# PowerManagement.net
KiCad netlist of a schematic drawn in Altium Designer
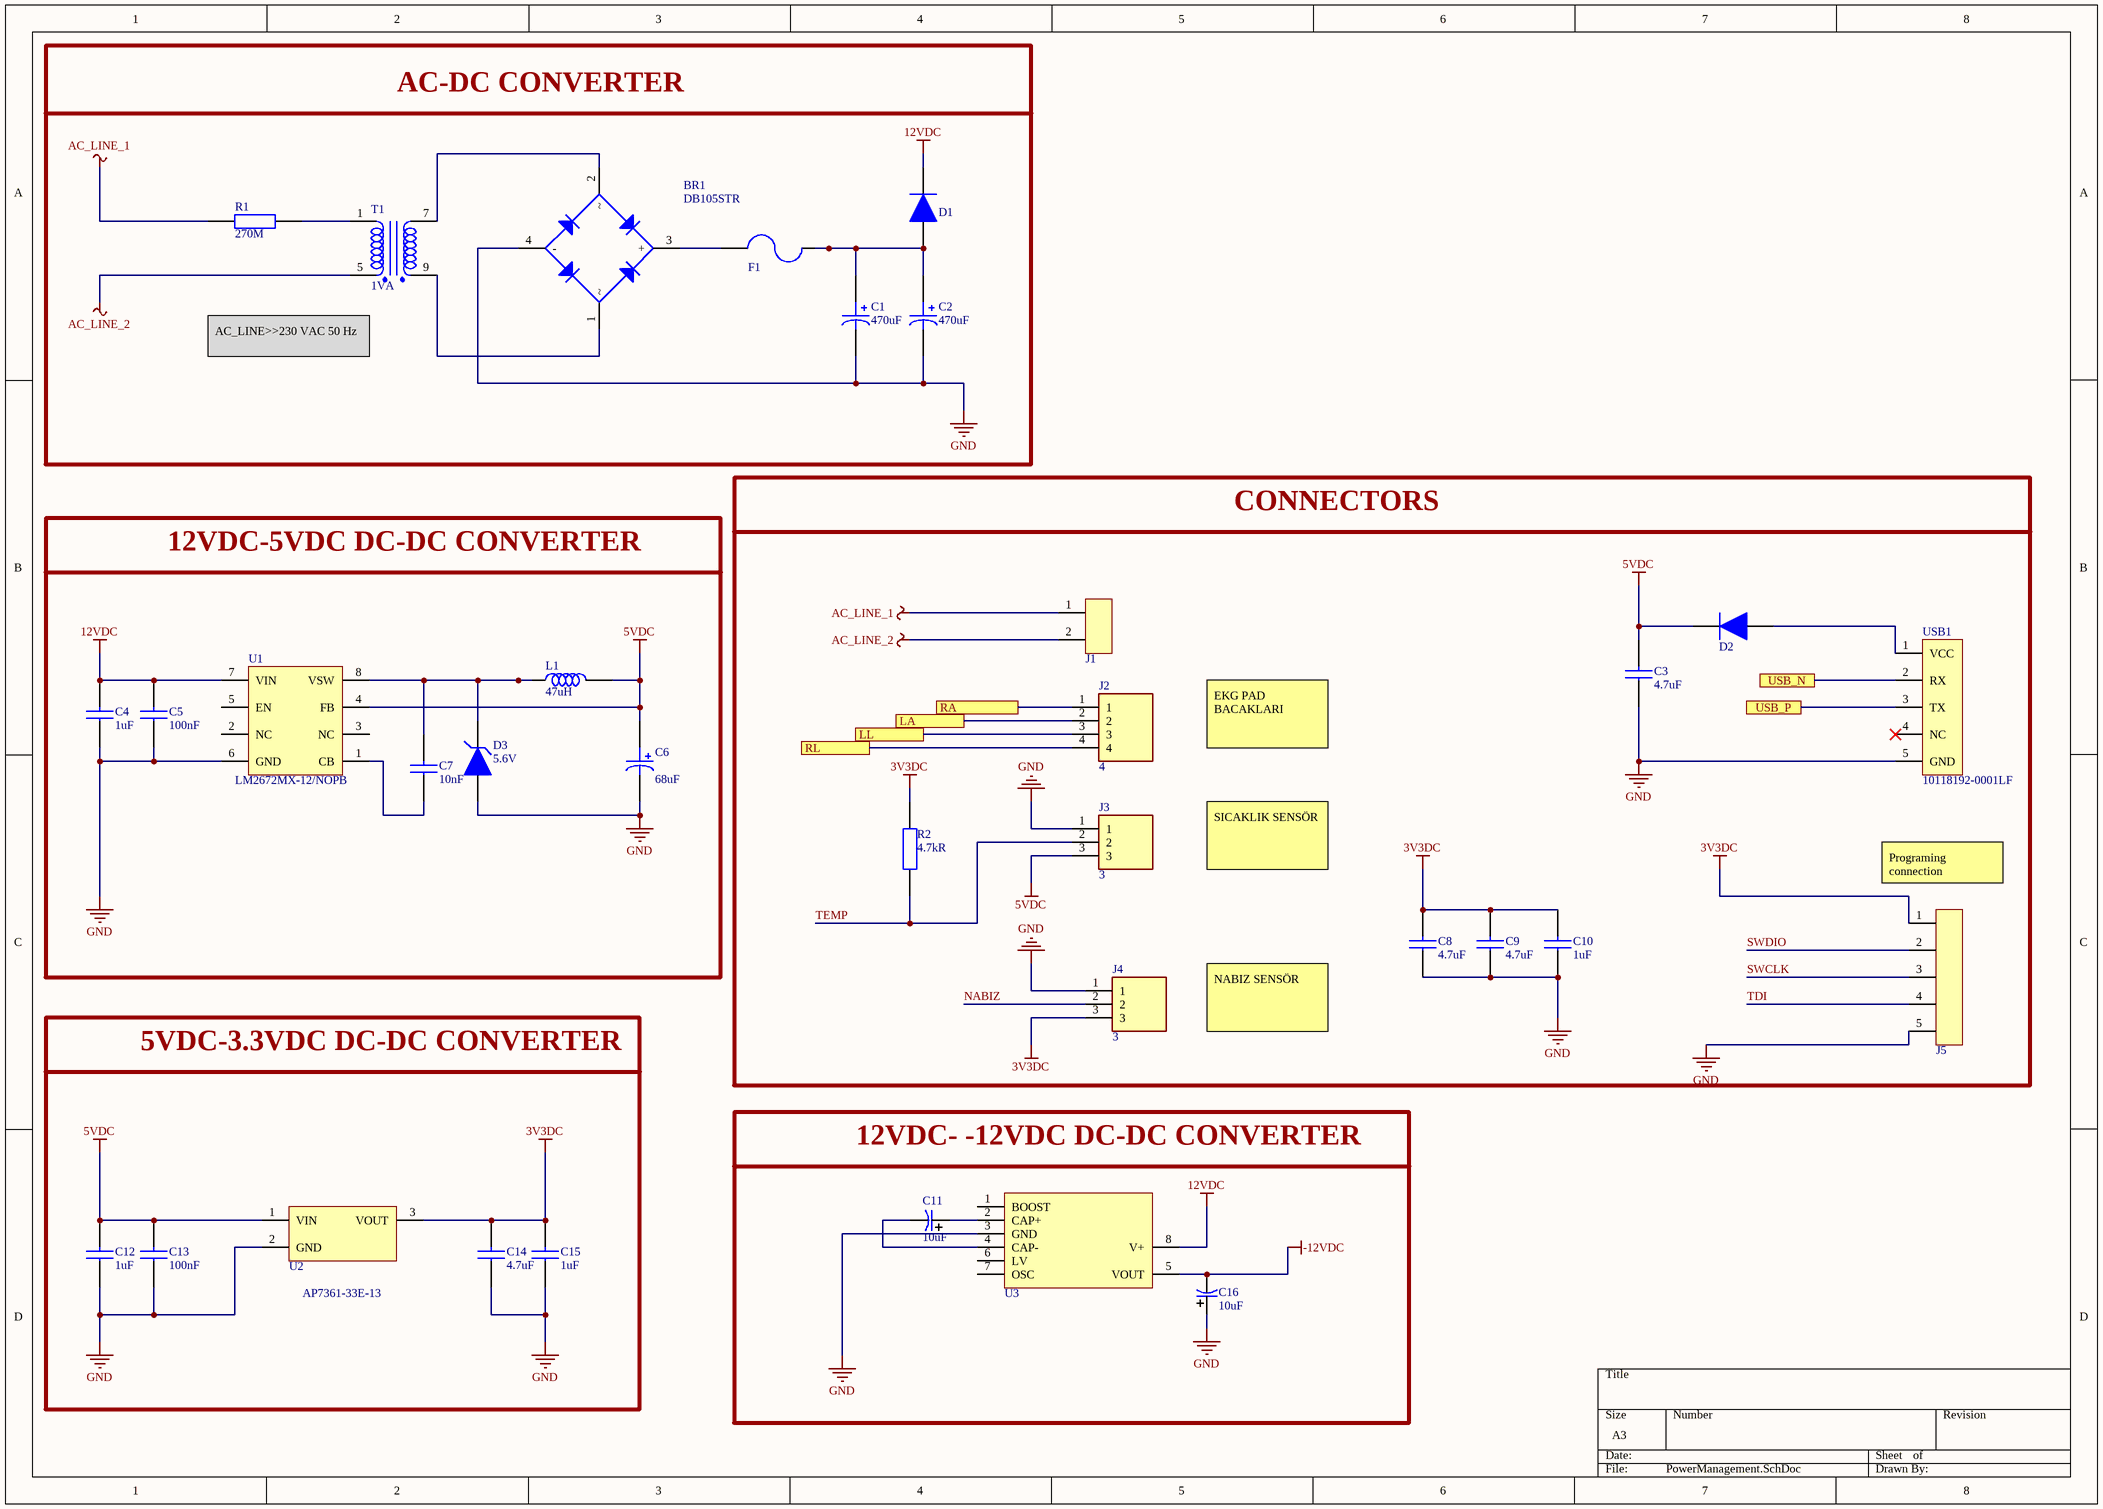
[diagram p0: PowerManagement.SchDoc]

(export (version "E")
  (design (tool "Eeschema 10.0.6"))
  (components
    (comp (ref "BR1")
      (value "DB105STR")
      (footprint "DB105STR")
      (fields (field (name "MANUFACTURER") "SMC") (field (name "DESIGNED BY") "TALAT"))
      (libsource (lib "Udemy_Library") (part "DB105STR"))
    )
    (comp (ref "C1")
      (value "ESH477M050AH4AA")
      (footprint "CAP_RADİAL_D10_P5")
      (description "Cap, 470UF, 50V, Alu Elec, Radial")
      (fields
        (field (name "MANUFACTURER") "KEMET")
        (field (name "TOLERANCE") "20%")
        (field (name "CAPACITANCE") "470uF")
        (field (name "DESIGNED BY") "TALAT")
      )
      (libsource (lib "Udemy_Library") (part "ESH477M050AH4AA"))
    )
    (comp (ref "C2")
      (value "ESH477M050AH4AA")
      (footprint "CAP_RADİAL_D10_P5")
      (description "Cap, 470UF, 50V, Alu Elec, Radial")
      (fields
        (field (name "MANUFACTURER") "KEMET")
        (field (name "TOLERANCE") "20%")
        (field (name "CAPACITANCE") "470uF")
        (field (name "DESIGNED BY") "TALAT")
      )
      (libsource (lib "Udemy_Library") (part "ESH477M050AH4AA"))
    )
    (comp (ref "C3")
      (value "CL21A475KAQNNNE")
      (footprint "CAP_0805")
      (description "CAP CER 4.7uF %10 0805")
      (fields
        (field (name "MANUFACTURER") "Samsung")
        (field (name "TOLERANCE") "10%")
        (field (name "CAPACITANCE") "4.7uF")
        (field (name "DESIGNED BY") "TALAT")
      )
      (libsource (lib "Udemy_Library") (part "CAP CER 4.7uF 0805"))
    )
    (comp (ref "C4")
      (value "CL21B105KBFNNNE")
      (footprint "CAP_0805")
      (description "CAP CER 1uF %10 0805")
      (fields
        (field (name "MANUFACTURER") "Samsung")
        (field (name "TOLERANCE") "10%")
        (field (name "CAPACITANCE") "1uF")
        (field (name "DESIGNED BY") "TALAT")
      )
      (libsource (lib "Udemy_Library") (part "CAP CER 1uF 0805"))
    )
    (comp (ref "C5")
      (value "CL21B104KBCNNNC")
      (footprint "CAP_0805")
      (description "CAP CER 100nF %10 0805")
      (fields
        (field (name "MANUFACTURER") "Samsung")
        (field (name "TOLERANCE") "10%")
        (field (name "CAPACITANCE") "100nF")
        (field (name "DESIGNED BY") "TALAT")
      )
      (libsource (lib "Udemy_Library") (part "CAP CER 100nF 0805"))
    )
    (comp (ref "C6")
      (value "EEV686M035A9HAA")
      (footprint "CAP_EEVseries")
      (description "Cap Aluminum Lytic 68uF 35V 20% (6.3 X 7.7mm) SMD 280mA 2000h 105C T/R")
      (fields
        (field (name "MANUFACTURER") "KEMET")
        (field (name "TOLERANCE") "20%")
        (field (name "CAPACITANCE") "68uF")
      )
      (libsource (lib "Udemy_Library") (part "CAP ALU 68uF"))
    )
    (comp (ref "C7")
      (value "0603B103K160CT")
      (footprint "CAP_0603")
      (description "CAP CER 10nF %10 0603")
      (fields
        (field (name "MANUFACTURER") "Walsin Technologies")
        (field (name "TOLERANCE") "10%")
        (field (name "CAPACITANCE") "10nF")
        (field (name "DESIGNED BY") "TALAT")
      )
      (libsource (lib "Udemy_Library") (part "CAP CER 10nF 0603"))
    )
    (comp (ref "C8")
      (value "CL21A475KAQNNNE")
      (footprint "CAP_0805")
      (description "CAP CER 4.7uF %10 0805")
      (fields
        (field (name "MANUFACTURER") "Samsung")
        (field (name "TOLERANCE") "10%")
        (field (name "CAPACITANCE") "4.7uF")
        (field (name "DESIGNED BY") "TALAT")
      )
      (libsource (lib "Udemy_Library") (part "CAP CER 4.7uF 0805"))
    )
    (comp (ref "C9")
      (value "CL21A475KAQNNNE")
      (footprint "CAP_0805")
      (description "CAP CER 4.7uF %10 0805")
      (fields
        (field (name "MANUFACTURER") "Samsung")
        (field (name "TOLERANCE") "10%")
        (field (name "CAPACITANCE") "4.7uF")
        (field (name "DESIGNED BY") "TALAT")
      )
      (libsource (lib "Udemy_Library") (part "CAP CER 4.7uF 0805"))
    )
    (comp (ref "C10")
      (value "CL21B105KBFNNNE")
      (footprint "CAP_0805")
      (description "CAP CER 1uF %10 0805")
      (fields
        (field (name "MANUFACTURER") "Samsung")
        (field (name "TOLERANCE") "10%")
        (field (name "CAPACITANCE") "1uF")
        (field (name "DESIGNED BY") "TALAT")
      )
      (libsource (lib "Udemy_Library") (part "CAP CER 1uF 0805"))
    )
    (comp (ref "C11")
      (value "CAP ALU 10uF")
      (footprint "A700V_KEM")
      (description "CAP ALUM POLY 10UF 20% 12.5V SMD")
      (fields
        (field (name "MANUFACTURER") "KEMET")
        (field (name "MANUFACTURER PART NUMBER") "A700V106M12RATE040")
        (field (name "CAPACITANCE") "10uF")
      )
      (libsource (lib "Udemy_Library") (part "CAP ALU 10uF"))
    )
    (comp (ref "C12")
      (value "CL21B105KBFNNNE")
      (footprint "CAP_0805")
      (description "CAP CER 1uF %10 0805")
      (fields
        (field (name "MANUFACTURER") "Samsung")
        (field (name "TOLERANCE") "10%")
        (field (name "CAPACITANCE") "1uF")
        (field (name "DESIGNED BY") "TALAT")
      )
      (libsource (lib "Udemy_Library") (part "CAP CER 1uF 0805"))
    )
    (comp (ref "C13")
      (value "C0603C104K5RACTU")
      (footprint "CAP_0603")
      (description "CAP CER 100nF %10 0603 SMD")
      (fields
        (field (name "MANUFACTURER") "KEMET")
        (field (name "CAPACITANCE") "100nF")
        (field (name "TOLERANCE") "10%")
        (field (name "DESIGNED BY") "TALAT")
      )
      (libsource (lib "Udemy_Library") (part "CAP CER 100nF 0603"))
    )
    (comp (ref "C14")
      (value "CL21A475KAQNNNE")
      (footprint "CAP_0805")
      (description "CAP CER 4.7uF %10 0805")
      (fields
        (field (name "MANUFACTURER") "Samsung")
        (field (name "TOLERANCE") "10%")
        (field (name "CAPACITANCE") "4.7uF")
        (field (name "DESIGNED BY") "TALAT")
      )
      (libsource (lib "Udemy_Library") (part "CAP CER 4.7uF 0805"))
    )
    (comp (ref "C15")
      (value "CL21B105KBFNNNE")
      (footprint "CAP_0805")
      (description "CAP CER 1uF %10 0805")
      (fields
        (field (name "MANUFACTURER") "Samsung")
        (field (name "TOLERANCE") "10%")
        (field (name "CAPACITANCE") "1uF")
        (field (name "DESIGNED BY") "TALAT")
      )
      (libsource (lib "Udemy_Library") (part "CAP CER 1uF 0805"))
    )
    (comp (ref "C16")
      (value "CAP ALU 10uF")
      (footprint "A700V_KEM")
      (description "CAP ALUM POLY 10UF 20% 12.5V SMD")
      (fields
        (field (name "MANUFACTURER") "KEMET")
        (field (name "MANUFACTURER PART NUMBER") "A700V106M12RATE040")
        (field (name "CAPACITANCE") "10uF")
      )
      (libsource (lib "Udemy_Library") (part "CAP ALU 10uF"))
    )
    (comp (ref "D1")
      (value "1N4148WS")
      (footprint "SOD323F")
      (description "Diode, Single, 75 V, 150 mA, 1 V, 4 ns")
      (fields
        (field (name "MANUFACTURER") "ON Semiconductor / Fairchild")
        (field (name "DESIGNED BY") "TALAT")
      )
      (libsource (lib "Udemy_Library") (part "1N4148WS"))
    )
    (comp (ref "D2")
      (value "1N4148WS")
      (footprint "SOD323F")
      (description "Diode, Single, 75 V, 150 mA, 1 V, 4 ns")
      (fields
        (field (name "MANUFACTURER") "ON Semiconductor / Fairchild")
        (field (name "DESIGNED BY") "TALAT")
      )
      (libsource (lib "Udemy_Library") (part "1N4148WS"))
    )
    (comp (ref "D3")
      (value "1SMB5919BT3G")
      (footprint "SMB")
      (description "Diode Zener Single 5.6V 5% 3W 2-Pin SMB T/R")
      (fields
        (field (name "MANUFACTURER") "ON Semiconductor")
        (field (name "TOLERANCE") "5%")
        (field (name "WORKING VOLTAGE") "5.6V")
        (field (name "DESIGNED BY") "TALAT")
      )
      (libsource (lib "Udemy_Library") (part "1SMB5919BT3G"))
    )
    (comp (ref "F1")
      (value "3413.0216.22")
      (footprint "3413.0216.2")
      (description "FUSE BRD MNT 1A 32VAC 63VDC 1206")
      (fields (field (name "MANUFACTURER") "Schurter") (field (name "DESIGNED BY") "TALAT"))
      (libsource (lib "Udemy_Library") (part "FUSE 3413.0216.22"))
    )
    (comp (ref "J1")
      (value "TBP01R1-508-02BE")
      (footprint "TBP01R1-508")
      (description "Conn Shrouded Header HDR 2 POS 5.08mm Solder RA Side Entry Thru-Hole Bag")
      (fields (field (name "MANUFACTURER") "CUI") (field (name "DESIGNED BY") "TALAT"))
      (libsource (lib "Udemy_Library") (part "TBP01R1-508-02BE"))
    )
    (comp (ref "J2") (value "4") (footprint "796644-4") (libsource (lib "Udemy_Library") (part "796644-4")))
    (comp (ref "J3")
      (value "3")
      (footprint "TBP01R1-508-03BE")
      (fields
        (field (name "MANUFACTURER") "CUI")
        (field (name "MANUFACTURER PART NUMBER") "TBP01R1-508-03BE")
      )
      (libsource (lib "Udemy_Library") (part "TBP01R1-508-03BE"))
    )
    (comp (ref "J4")
      (value "3")
      (footprint "TBP01R1-508-03BE")
      (fields
        (field (name "MANUFACTURER") "CUI")
        (field (name "MANUFACTURER PART NUMBER") "TBP01R1-508-03BE")
      )
      (libsource (lib "Udemy_Library") (part "TBP01R1-508-03BE"))
    )
    (comp (ref "J5")
      (value "SMH-105-02-L-S")
      (footprint "PINHEADER1X5_RA")
      (description ".100 C.L. HORIZONTAL SMT SOCKET")
      (fields (field (name "MANUFACTURER") "Samtec") (field (name "DESIGNED BY") "TALAT"))
      (libsource (lib "Udemy_Library") (part "SMH-105-02-L-S"))
    )
    (comp (ref "L1")
      (value "78438335470")
      (footprint "IND_1212")
      (description "FIXED IND 47UH 390MA 2.3 OHM SMD")
      (fields
        (field (name "MANUFACTURER") "Wurth Electronics")
        (field (name "TOLERANCE") "30%")
        (field (name "INDUCTANCE") "47uH")
        (field (name "DESIGNED BY") "TALAT")
      )
      (libsource (lib "Udemy_Library") (part "IND 47uH"))
    )
    (comp (ref "R1")
      (value "5WD27")
      (footprint "RES_AXIAL_W")
      (description "Resistor 5 Watt Cermet Wirewound Flameproof .27 Ohm 5% Axial Lead")
      (fields
        (field (name "MANUFACTURER") "NTE Electronics")
        (field (name "TOLERANCE") "5%")
        (field (name "RESISTANCE") "270M")
        (field (name "DESIGNED BY") "TALAT")
      )
      (libsource (lib "Udemy_Library") (part "5WD27"))
    )
    (comp (ref "R2")
      (value "RC0603JR-074K7L")
      (footprint "RES_0603")
      (description "RES 4K7 %5 OHM 0603 SMD")
      (fields
        (field (name "MANUFACTURER") "Yageo")
        (field (name "TOLERANCE") "5%")
        (field (name "RESISTANCE") "4.7kR")
        (field (name "DESIGNED BY") "TALAT")
      )
      (libsource (lib "Udemy_Library") (part "RES 4K7 OHM 0603"))
    )
    (comp (ref "T1")
      (value "BV302S12010-ZU")
      (footprint "BV302S")
      (description "PWR XFMR LAMINATED 1VA TH")
      (fields
        (field (name "MANUFACTURER") "Zettler Magnetics")
        (field (name "RATED POWER") "1VA")
        (field (name "DESIGNED BY") "TALAT")
      )
      (libsource (lib "Udemy_Library") (part "BV302S12010-ZU"))
    )
    (comp (ref "U1")
      (value "LM2672MX-12/NOPB")
      (footprint "SOIC8")
      (description "IC REG BUCK 12V 1A 8-SOIC")
      (fields (field (name "MANUFACTURER") "TI National Semiconductor") (field (name "DESIGNED BY") "TALAT"))
      (libsource (lib "Udemy_Library") (part "LM2672MX-12/NOPB"))
    )
    (comp (ref "U2")
      (value "AP7361-33E-13")
      (footprint "SOT223")
      (description "LDO Regulator Pos 3.3V 1A 4-Pin(3+Tab) SOT-223 T/R")
      (fields (field (name "MANUFACTURER") "Diodes") (field (name "DESIGNED BY") "TALAT"))
      (libsource (lib "Udemy_Library") (part "AP7361-33E-13"))
    )
    (comp (ref "U3")
      (value "LTC1044AIS8#TRPBF")
      (footprint "SOIC8")
      (description "IC REG SWTCHD CAP INV 20MA 8SOIC")
      (fields
        (field (name "MANUFACTURER") "Analog Devices / Linear Technology")
        (field (name "DESIGNED BY") "Talat")
      )
      (libsource (lib "Udemy_Library") (part "LTC1044A"))
    )
    (comp (ref "USB1")
      (value "10118192-0001LF")
      (footprint "MICRO_B_USB")
      (description "CONN RCPT USB2.0 MICRO B SMD R/A")
      (fields (field (name "MANUFACTURER") "Amphenol FCI") (field (name "DESIGNED BY") "TALAT"))
      (libsource (lib "Udemy_Library") (part "Micro B USB Connector"))
    )
  )
  (nets
    (net (code "1") (name "-12VDC") (class "Default")
      (node (ref "C16") (pin "2") (pinfunction "2_2") (pintype "passive"))
      (node (ref "U3") (pin "5") (pinfunction "VOUT_5") (pintype "passive"))
    )
    (net (code "2") (name "/LA") (class "Default")
      (node (ref "J2") (pin "2") (pinfunction "2_2") (pintype "passive"))
    )
    (net (code "3") (name "/LL") (class "Default")
      (node (ref "J2") (pin "3") (pinfunction "3_3") (pintype "passive"))
    )
    (net (code "4") (name "/NABIZ") (class "Default")
      (node (ref "J4") (pin "2") (pinfunction "2_2") (pintype "passive"))
    )
    (net (code "5") (name "/RA") (class "Default")
      (node (ref "J2") (pin "1") (pinfunction "1_1") (pintype "passive"))
    )
    (net (code "6") (name "/RL") (class "Default")
      (node (ref "J2") (pin "4") (pinfunction "4_4") (pintype "passive"))
    )
    (net (code "7") (name "/SWCLK") (class "Default")
      (node (ref "J5") (pin "3") (pinfunction "3_3") (pintype "power_in"))
    )
    (net (code "8") (name "/SWDIO") (class "Default")
      (node (ref "J5") (pin "2") (pinfunction "2_2") (pintype "power_in"))
    )
    (net (code "9") (name "/TDI") (class "Default")
      (node (ref "J5") (pin "4") (pinfunction "4_4") (pintype "power_in"))
    )
    (net (code "10") (name "/TEMP") (class "Default")
      (node (ref "J3") (pin "2") (pinfunction "2_2") (pintype "passive"))
      (node (ref "R2") (pin "1") (pinfunction "1_1") (pintype "passive"))
    )
    (net (code "11") (name "/USB_N") (class "Default")
      (node (ref "USB1") (pin "2") (pinfunction "RX_2") (pintype "power_in"))
    )
    (net (code "12") (name "/USB_P") (class "Default")
      (node (ref "USB1") (pin "3") (pinfunction "TX_3") (pintype "power_in"))
    )
    (net (code "13") (name "3V3DC") (class "Default")
      (node (ref "C10") (pin "2") (pinfunction "2_2") (pintype "passive"))
      (node (ref "C14") (pin "2") (pinfunction "2_2") (pintype "passive"))
      (node (ref "C15") (pin "2") (pinfunction "2_2") (pintype "passive"))
      (node (ref "C8") (pin "2") (pinfunction "2_2") (pintype "passive"))
      (node (ref "C9") (pin "2") (pinfunction "2_2") (pintype "passive"))
      (node (ref "J4") (pin "3") (pinfunction "3_3") (pintype "passive"))
      (node (ref "J5") (pin "1") (pinfunction "1_1") (pintype "power_in"))
      (node (ref "R2") (pin "2") (pinfunction "2_2") (pintype "passive"))
      (node (ref "U2") (pin "3") (pinfunction "VOUT_3") (pintype "passive"))
    )
    (net (code "14") (name "5VDC") (class "Default")
      (node (ref "C12") (pin "2") (pinfunction "2_2") (pintype "passive"))
      (node (ref "C13") (pin "2") (pinfunction "2_2") (pintype "passive"))
      (node (ref "C3") (pin "2") (pinfunction "2_2") (pintype "passive"))
      (node (ref "C6") (pin "1") (pinfunction "1_1") (pintype "passive"))
      (node (ref "D2") (pin "1") (pinfunction "1_1") (pintype "power_in"))
      (node (ref "J3") (pin "3") (pinfunction "3_3") (pintype "passive"))
      (node (ref "L1") (pin "2") (pinfunction "2_2") (pintype "passive"))
      (node (ref "U1") (pin "4") (pinfunction "FB_4") (pintype "passive"))
      (node (ref "U2") (pin "1") (pinfunction "VIN_1") (pintype "passive"))
    )
    (net (code "15") (name "12VDC") (class "Default")
      (node (ref "C4") (pin "2") (pinfunction "2_2") (pintype "passive"))
      (node (ref "C5") (pin "2") (pinfunction "2_2") (pintype "passive"))
      (node (ref "D1") (pin "1") (pinfunction "1_1") (pintype "power_in"))
      (node (ref "U1") (pin "7") (pinfunction "VIN_7") (pintype "passive"))
      (node (ref "U3") (pin "8") (pinfunction "V+_8") (pintype "passive"))
    )
    (net (code "16") (name "AC_LINE_1") (class "Default")
      (node (ref "J1") (pin "1") (pinfunction "1_1") (pintype "power_in"))
      (node (ref "R1") (pin "1") (pinfunction "1_1") (pintype "passive"))
    )
    (net (code "17") (name "AC_LINE_2") (class "Default")
      (node (ref "J1") (pin "2") (pinfunction "2_2") (pintype "power_in"))
      (node (ref "T1") (pin "5") (pinfunction "5_5") (pintype "passive"))
    )
    (net (code "18") (name "GND") (class "Default")
      (node (ref "BR1") (pin "4") (pinfunction "-_4") (pintype "passive"))
      (node (ref "C1") (pin "2") (pinfunction "2_2") (pintype "passive"))
      (node (ref "C10") (pin "1") (pinfunction "1_1") (pintype "passive"))
      (node (ref "C12") (pin "1") (pinfunction "1_1") (pintype "passive"))
      (node (ref "C13") (pin "1") (pinfunction "1_1") (pintype "passive"))
      (node (ref "C14") (pin "1") (pinfunction "1_1") (pintype "passive"))
      (node (ref "C15") (pin "1") (pinfunction "1_1") (pintype "passive"))
      (node (ref "C16") (pin "1") (pinfunction "1_1") (pintype "passive"))
      (node (ref "C2") (pin "2") (pinfunction "2_2") (pintype "passive"))
      (node (ref "C3") (pin "1") (pinfunction "1_1") (pintype "passive"))
      (node (ref "C4") (pin "1") (pinfunction "1_1") (pintype "passive"))
      (node (ref "C5") (pin "1") (pinfunction "1_1") (pintype "passive"))
      (node (ref "C6") (pin "2") (pinfunction "2_2") (pintype "passive"))
      (node (ref "C8") (pin "1") (pinfunction "1_1") (pintype "passive"))
      (node (ref "C9") (pin "1") (pinfunction "1_1") (pintype "passive"))
      (node (ref "D3") (pin "A") (pinfunction "A_A") (pintype "passive"))
      (node (ref "J3") (pin "1") (pinfunction "1_1") (pintype "passive"))
      (node (ref "J4") (pin "1") (pinfunction "1_1") (pintype "passive"))
      (node (ref "J5") (pin "5") (pinfunction "5_5") (pintype "power_in"))
      (node (ref "U1") (pin "6") (pinfunction "GND_6") (pintype "passive"))
      (node (ref "U2") (pin "2") (pinfunction "GND_2") (pintype "passive"))
      (node (ref "U3") (pin "3") (pinfunction "GND_3") (pintype "passive"))
      (node (ref "USB1") (pin "5") (pinfunction "GND_5") (pintype "power_in"))
    )
    (net (code "19") (name "Net-(BR1-+)") (class "Default")
      (node (ref "BR1") (pin "3") (pinfunction "+_3") (pintype "passive"))
      (node (ref "F1") (pin "1") (pinfunction "1_1") (pintype "passive"))
    )
    (net (code "20") (name "Net-(BR1-~-Pad1)") (class "Default")
      (node (ref "BR1") (pin "1") (pinfunction "~_1") (pintype "passive"))
      (node (ref "T1") (pin "9") (pinfunction "9_9") (pintype "passive"))
    )
    (net (code "21") (name "Net-(BR1-~-Pad2)") (class "Default")
      (node (ref "BR1") (pin "2") (pinfunction "~_2") (pintype "passive"))
      (node (ref "T1") (pin "7") (pinfunction "7_7") (pintype "passive"))
    )
    (net (code "22") (name "Net-(C1-Pad1)") (class "Default")
      (node (ref "C1") (pin "1") (pinfunction "1_1") (pintype "passive"))
      (node (ref "C2") (pin "1") (pinfunction "1_1") (pintype "passive"))
      (node (ref "D1") (pin "2") (pinfunction "2_2") (pintype "power_in"))
      (node (ref "F1") (pin "2") (pinfunction "2_2") (pintype "passive"))
    )
    (net (code "23") (name "Net-(R1-Pad2)") (class "Default")
      (node (ref "R1") (pin "2") (pinfunction "2_2") (pintype "passive"))
      (node (ref "T1") (pin "1") (pinfunction "1_1") (pintype "passive"))
    )
    (net (code "24") (name "Net-(U1-CB)") (class "Default")
      (node (ref "C7") (pin "1") (pinfunction "1_1") (pintype "passive"))
      (node (ref "U1") (pin "1") (pinfunction "CB_1") (pintype "passive"))
    )
    (net (code "25") (name "Net-(U1-VSW)") (class "Default")
      (node (ref "C7") (pin "2") (pinfunction "2_2") (pintype "passive"))
      (node (ref "D3") (pin "C") (pinfunction "C_C") (pintype "passive"))
      (node (ref "L1") (pin "1") (pinfunction "1_1") (pintype "passive"))
      (node (ref "U1") (pin "8") (pinfunction "VSW_8") (pintype "passive"))
    )
    (net (code "26") (name "Net-(U3-CAP+)") (class "Default")
      (node (ref "C11") (pin "1") (pinfunction "1_1") (pintype "passive"))
      (node (ref "U3") (pin "2") (pinfunction "CAP+_2") (pintype "passive"))
    )
    (net (code "27") (name "Net-(U3-CAP-)") (class "Default")
      (node (ref "C11") (pin "2") (pinfunction "2_2") (pintype "passive"))
      (node (ref "U3") (pin "4") (pinfunction "CAP-_4") (pintype "passive"))
    )
    (net (code "28") (name "Net-(USB1-VCC)") (class "Default")
      (node (ref "D2") (pin "2") (pinfunction "2_2") (pintype "power_in"))
      (node (ref "USB1") (pin "1") (pinfunction "VCC_1") (pintype "power_in"))
    )
    (net (code "29") (name "unconnected-(U1-EN-Pad5)") (class "Default")
      (node (ref "U1") (pin "5") (pinfunction "EN_5") (pintype "passive"))
    )
    (net (code "30") (name "unconnected-(U1-NC-Pad2)") (class "Default")
      (node (ref "U1") (pin "2") (pinfunction "NC_2") (pintype "passive"))
    )
    (net (code "31") (name "unconnected-(U1-NC-Pad3)") (class "Default")
      (node (ref "U1") (pin "3") (pinfunction "NC_3") (pintype "passive"))
    )
    (net (code "32") (name "unconnected-(U3-BOOST-Pad1)") (class "Default")
      (node (ref "U3") (pin "1") (pinfunction "BOOST_1") (pintype "passive"))
    )
    (net (code "33") (name "unconnected-(U3-LV-Pad6)") (class "Default")
      (node (ref "U3") (pin "6") (pinfunction "LV_6") (pintype "passive"))
    )
    (net (code "34") (name "unconnected-(U3-OSC-Pad7)") (class "Default")
      (node (ref "U3") (pin "7") (pinfunction "OSC_7") (pintype "passive"))
    )
    (net (code "35") (name "unconnected-(USB1-NC-Pad4)") (class "Default")
      (node (ref "USB1") (pin "4") (pinfunction "NC_4") (pintype "power_in+no_connect"))
    )
  )
)
